# POWER.net
KiCad netlist of a schematic drawn in Altium Designer
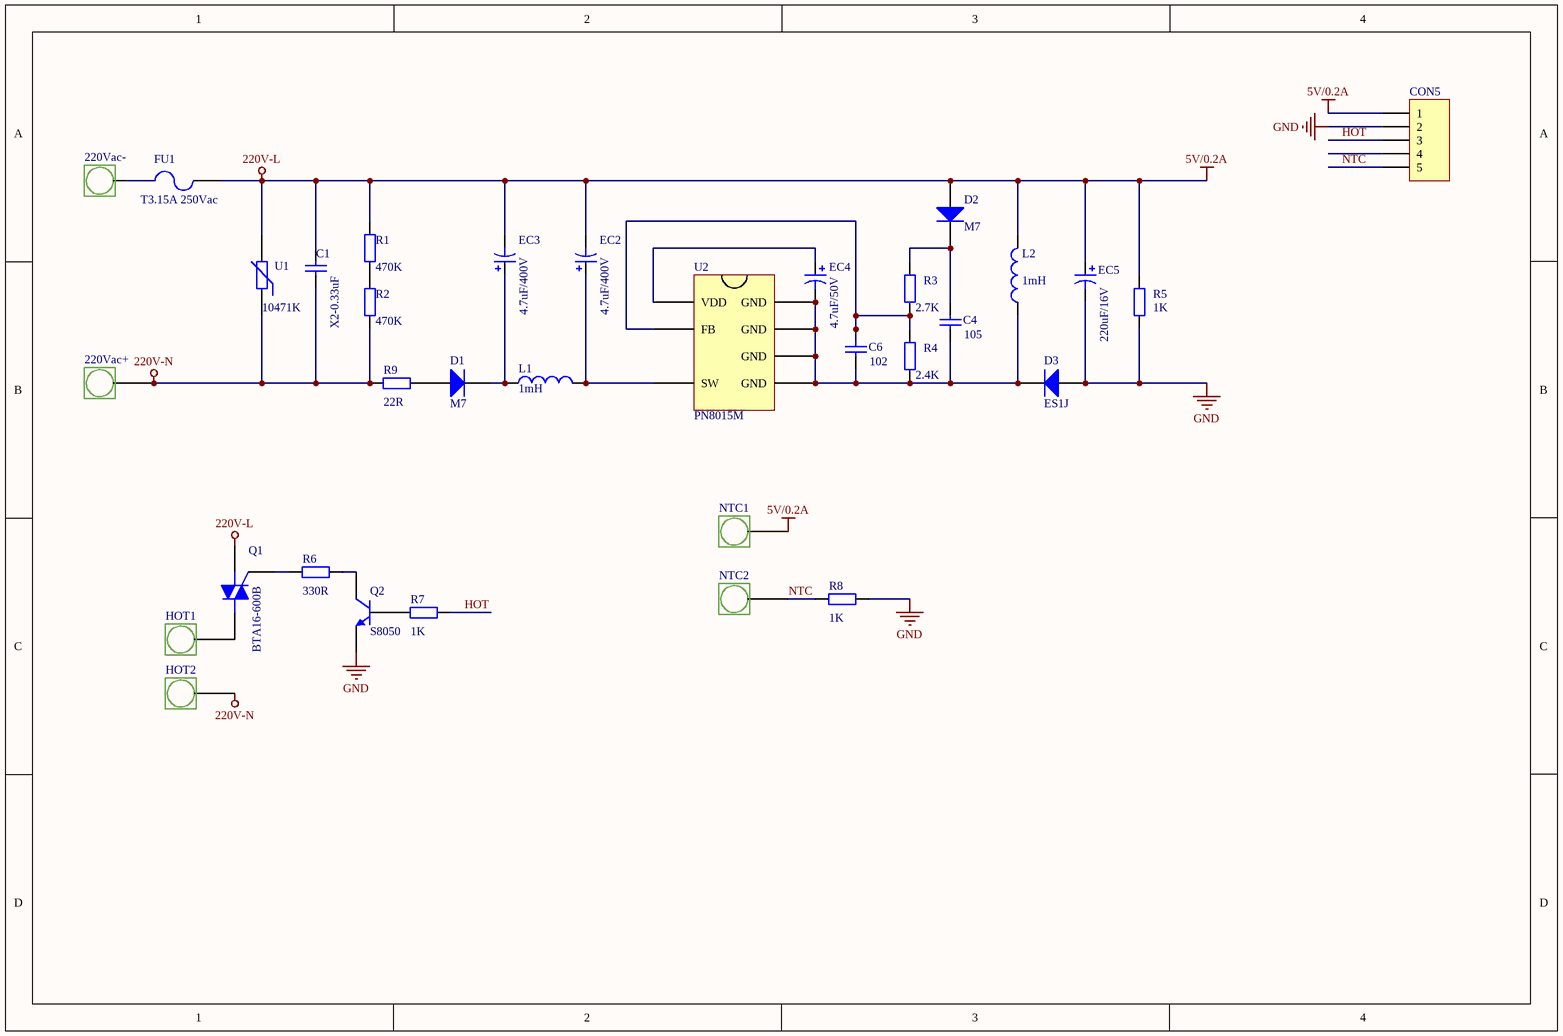
[diagram p0: POWER.SchDoc]

(export (version "E")
  (design (tool "Eeschema 10.0.6"))
  (components
    (comp (ref "220Vac+") (value "焊接点") (footprint "HanJie") (libsource (lib "HT_SHUIHU") (part "PORT")))
    (comp (ref "220Vac-") (value "焊接点") (footprint "HanJie") (libsource (lib "HT_SHUIHU") (part "PORT")))
    (comp (ref "C1")
      (value "X2-0.33uF")
      (footprint "X2-AnGuiDianRong")
      (description "Capacitor")
      (fields (field (name "PUBLISHER") "Altium Limited"))
      (libsource (lib "Miscellaneous Devices") (part "Cap"))
    )
    (comp (ref "C4")
      (value "105")
      (footprint "6-0805_N")
      (description "Capacitor")
      (fields (field (name "Comment") "电容") (field (name "PUBLISHER") "Altium Limited"))
      (libsource (lib "Miscellaneous Devices") (part "Cap"))
    )
    (comp (ref "C6")
      (value "102")
      (footprint "6-0805_N")
      (description "Capacitor")
      (fields (field (name "Comment") "电容") (field (name "PUBLISHER") "Altium Limited"))
      (libsource (lib "Miscellaneous Devices") (part "Cap"))
    )
    (comp (ref "CON5")
      (value "连接器")
      (footprint "HEADER_5")
      (description "Header, 5-Pin")
      (fields (field (name "PUBLISHER") "Altium Limited"))
      (libsource (lib "Miscellaneous Connectors") (part "Header 5"))
    )
    (comp (ref "D1")
      (value "M7")
      (footprint "ErJiGuan-M7")
      (description "1 Amp General Purpose Rectifier")
      (fields (field (name "PUBLISHER") "Altium Limited"))
      (libsource (lib "Miscellaneous Devices") (part "Diode 1N4001"))
    )
    (comp (ref "D2")
      (value "M7")
      (footprint "ErJiGuan-M7")
      (description "1 Amp General Purpose Rectifier")
      (fields (field (name "PUBLISHER") "Altium Limited"))
      (libsource (lib "Miscellaneous Devices") (part "Diode 1N4007"))
    )
    (comp (ref "D3")
      (value "ES1J")
      (footprint "ErJiGuan-M7")
      (description "Default Diode")
      (fields (field (name "PUBLISHER") "Altium Limited"))
      (libsource (lib "Miscellaneous Devices") (part "Diode"))
    )
    (comp (ref "EC2")
      (value "4.7uF/400V")
      (footprint "DianRong-3.5mm")
      (description "Polarized Capacitor (Radial)")
      (fields (field (name "Comment") "电容") (field (name "PUBLISHER") "Altium Limited"))
      (libsource (lib "Miscellaneous Devices") (part "Cap Pol1"))
    )
    (comp (ref "EC3")
      (value "4.7uF/400V")
      (footprint "DianRong-3.5mm")
      (description "Polarized Capacitor (Radial)")
      (fields (field (name "Comment") "电容") (field (name "PUBLISHER") "Altium Limited"))
      (libsource (lib "Miscellaneous Devices") (part "Cap Pol1"))
    )
    (comp (ref "EC4")
      (value "4.7uF/50V")
      (footprint "DianRong-3.3mm")
      (description "Polarized Capacitor (Radial)")
      (fields (field (name "Comment") "电容") (field (name "PUBLISHER") "Altium Limited"))
      (libsource (lib "Miscellaneous Devices") (part "Cap Pol1"))
    )
    (comp (ref "EC5")
      (value "220uF/16V")
      (footprint "DianRong-3.2mm")
      (description "Polarized Capacitor (Radial)")
      (fields (field (name "Comment") "电容") (field (name "PUBLISHER") "Altium Limited"))
      (libsource (lib "Miscellaneous Devices") (part "Cap Pol1"))
    )
    (comp (ref "FU1")
      (value "T3.15A 250Vac")
      (footprint "BaoXianSi")
      (description "Fuse")
      (fields (field (name "PUBLISHER") "Altium Limited"))
      (libsource (lib "Miscellaneous Devices") (part "Fuse 2"))
    )
    (comp (ref "HOT1") (value "焊接点") (footprint "HanJie") (libsource (lib "HT_SHUIHU") (part "PORT")))
    (comp (ref "HOT2") (value "焊接点") (footprint "HanJie") (libsource (lib "HT_SHUIHU") (part "PORT")))
    (comp (ref "L1")
      (value "1mH")
      (footprint "DianGan-12.5mm")
      (description "Inductor")
      (fields (field (name "Comment") "电感") (field (name "PUBLISHER") "Altium Limited"))
      (libsource (lib "Miscellaneous Devices") (part "Inductor"))
    )
    (comp (ref "L2")
      (value "1mH")
      (footprint "DianGan")
      (description "Inductor")
      (fields (field (name "Comment") "电感") (field (name "PUBLISHER") "Altium Limited"))
      (libsource (lib "Miscellaneous Devices") (part "Inductor"))
    )
    (comp (ref "NTC1") (value "焊接点") (footprint "HanJie") (libsource (lib "HT_SHUIHU") (part "PORT")))
    (comp (ref "NTC2") (value "焊接点") (footprint "HanJie") (libsource (lib "HT_SHUIHU") (part "PORT")))
    (comp (ref "Q1")
      (value "BTA16-600B")
      (footprint "BTA16-600B")
      (description "Silicon Bidirectional Triode Thyristor")
      (fields (field (name "PUBLISHER") "Altium Limited"))
      (libsource (lib "Miscellaneous Devices") (part "Triac"))
    )
    (comp (ref "Q2")
      (value "S8050")
      (footprint "SOT-23_L")
      (description "NPN Bipolar Transistor")
      (fields (field (name "PUBLISHER") "Altium Limited"))
      (libsource (lib "Miscellaneous Devices") (part "QNPN"))
    )
    (comp (ref "R1")
      (value "470K")
      (footprint "6-0805_N")
      (description "Resistor")
      (fields (field (name "Comment") "电阻") (field (name "PUBLISHER") "Altium Limited"))
      (libsource (lib "") (part "Res2_1"))
    )
    (comp (ref "R2")
      (value "470K")
      (footprint "6-0805_N")
      (description "Resistor")
      (fields (field (name "Comment") "电阻") (field (name "PUBLISHER") "Altium Limited"))
      (libsource (lib "") (part "Res2_1"))
    )
    (comp (ref "R3")
      (value "2.7K")
      (footprint "6-0805_N")
      (description "Resistor")
      (fields (field (name "Comment") "电阻") (field (name "PUBLISHER") "Altium Limited"))
      (libsource (lib "") (part "Res2_1"))
    )
    (comp (ref "R4")
      (value "2.4K")
      (footprint "6-0805_N")
      (description "Resistor")
      (fields (field (name "Comment") "电阻") (field (name "PUBLISHER") "Altium Limited"))
      (libsource (lib "") (part "Res2_1"))
    )
    (comp (ref "R5")
      (value "1K")
      (footprint "6-0805_N")
      (description "Resistor")
      (fields (field (name "Comment") "电阻") (field (name "PUBLISHER") "Altium Limited"))
      (libsource (lib "") (part "Res2_1"))
    )
    (comp (ref "R6")
      (value "330R")
      (footprint "6-0805_N")
      (description "Resistor")
      (fields (field (name "Comment") "电阻") (field (name "PUBLISHER") "Altium Limited"))
      (libsource (lib "Miscellaneous Devices") (part "Res2"))
    )
    (comp (ref "R7")
      (value "1K")
      (footprint "6-0805_N")
      (description "Resistor")
      (fields (field (name "Comment") "电阻") (field (name "PUBLISHER") "Altium Limited"))
      (libsource (lib "Miscellaneous Devices") (part "Res2"))
    )
    (comp (ref "R8")
      (value "1K")
      (footprint "6-0805_N")
      (description "Resistor")
      (fields (field (name "Comment") "电阻") (field (name "PUBLISHER") "Altium Limited"))
      (libsource (lib "Miscellaneous Devices") (part "Res2"))
    )
    (comp (ref "R9")
      (value "22R")
      (footprint "DianZhu-20mm")
      (description "Resistor")
      (fields (field (name "Comment") "电阻") (field (name "PUBLISHER") "Altium Limited"))
      (libsource (lib "Miscellaneous Devices") (part "Res2"))
    )
    (comp (ref "U1")
      (value "10471K")
      (footprint "YaMinDianZhu")
      (description "Varistor (Voltage-Sensitive Resistor)")
      (fields (field (name "PUBLISHER") "Altium Limited"))
      (libsource (lib "Miscellaneous Devices") (part "Res Varistor"))
    )
    (comp (ref "U2")
      (value "PN8015M")
      (footprint "SOP7-PN8015M")
      (libsource (lib "HT_SHUIHU") (part "PN8015"))
    )
  )
  (nets
    (net (code "1") (name "/HOT") (class "Default")
      (node (ref "CON5") (pin "3") (pinfunction "3_3") (pintype "passive"))
      (node (ref "R7") (pin "2") (pinfunction "2_2") (pintype "passive"))
    )
    (net (code "2") (name "/NTC") (class "Default")
      (node (ref "CON5") (pin "5") (pinfunction "5_5") (pintype "passive"))
      (node (ref "NTC2") (pin "1") (pinfunction "P_1") (pintype "passive"))
      (node (ref "R8") (pin "1") (pinfunction "1_1") (pintype "passive"))
    )
    (net (code "3") (name "220V-L") (class "Default")
      (node (ref "C1") (pin "2") (pinfunction "2_2") (pintype "passive"))
      (node (ref "CON5") (pin "1") (pinfunction "1_1") (pintype "passive"))
      (node (ref "D2") (pin "1") (pinfunction "A_1") (pintype "passive"))
      (node (ref "EC2") (pin "2") (pinfunction "2_2") (pintype "passive"))
      (node (ref "EC3") (pin "2") (pinfunction "2_2") (pintype "passive"))
      (node (ref "EC5") (pin "1") (pinfunction "1_1") (pintype "passive"))
      (node (ref "FU1") (pin "2") (pinfunction "2_2") (pintype "passive"))
      (node (ref "L2") (pin "2") (pinfunction "2_2") (pintype "passive"))
      (node (ref "NTC1") (pin "1") (pinfunction "P_1") (pintype "passive"))
      (node (ref "Q1") (pin "1") (pinfunction "M1_1") (pintype "passive"))
      (node (ref "R1") (pin "2") (pinfunction "2_2") (pintype "passive"))
      (node (ref "R5") (pin "2") (pinfunction "2_2") (pintype "passive"))
      (node (ref "U1") (pin "2") (pinfunction "2_2") (pintype "passive"))
    )
    (net (code "4") (name "220V-N") (class "Default")
      (node (ref "220Vac+") (pin "1") (pinfunction "P_1") (pintype "passive"))
      (node (ref "C1") (pin "1") (pinfunction "1_1") (pintype "passive"))
      (node (ref "HOT2") (pin "1") (pinfunction "P_1") (pintype "passive"))
      (node (ref "R2") (pin "1") (pinfunction "1_1") (pintype "passive"))
      (node (ref "R9") (pin "1") (pinfunction "1_1") (pintype "passive"))
      (node (ref "U1") (pin "1") (pinfunction "1_1") (pintype "passive"))
    )
    (net (code "5") (name "GND") (class "Default")
      (node (ref "CON5") (pin "2") (pinfunction "2_2") (pintype "passive"))
      (node (ref "D3") (pin "1") (pinfunction "A_1") (pintype "passive"))
      (node (ref "EC5") (pin "2") (pinfunction "2_2") (pintype "passive"))
      (node (ref "Q2") (pin "2") (pinfunction "E_2") (pintype "passive"))
      (node (ref "R5") (pin "1") (pinfunction "1_1") (pintype "passive"))
      (node (ref "R8") (pin "2") (pinfunction "2_2") (pintype "passive"))
    )
    (net (code "6") (name "Net-(220Vac--P)") (class "Default")
      (node (ref "220Vac-") (pin "1") (pinfunction "P_1") (pintype "passive"))
      (node (ref "FU1") (pin "1") (pinfunction "1_1") (pintype "passive"))
    )
    (net (code "7") (name "Net-(D1-A)") (class "Default")
      (node (ref "D1") (pin "1") (pinfunction "A_1") (pintype "passive"))
      (node (ref "R9") (pin "2") (pinfunction "2_2") (pintype "passive"))
    )
    (net (code "8") (name "Net-(D1-K)") (class "Default")
      (node (ref "D1") (pin "2") (pinfunction "K_2") (pintype "passive"))
      (node (ref "EC3") (pin "1") (pinfunction "1_1") (pintype "passive"))
      (node (ref "L1") (pin "1") (pinfunction "1_1") (pintype "passive"))
    )
    (net (code "9") (name "Net-(D2-K)") (class "Default")
      (node (ref "C4") (pin "2") (pinfunction "2_2") (pintype "passive"))
      (node (ref "D2") (pin "2") (pinfunction "K_2") (pintype "passive"))
      (node (ref "R3") (pin "2") (pinfunction "2_2") (pintype "passive"))
    )
    (net (code "10") (name "Net-(D3-K)") (class "Default")
      (node (ref "C4") (pin "1") (pinfunction "1_1") (pintype "passive"))
      (node (ref "C6") (pin "1") (pinfunction "1_1") (pintype "passive"))
      (node (ref "D3") (pin "2") (pinfunction "K_2") (pintype "passive"))
      (node (ref "EC4") (pin "2") (pinfunction "2_2") (pintype "passive"))
      (node (ref "L2") (pin "1") (pinfunction "1_1") (pintype "passive"))
      (node (ref "R4") (pin "1") (pinfunction "1_1") (pintype "passive"))
      (node (ref "U2") (pin "4") (pinfunction "GND_4") (pintype "passive"))
      (node (ref "U2") (pin "5") (pinfunction "GND_5") (pintype "passive"))
      (node (ref "U2") (pin "6") (pinfunction "GND_6") (pintype "passive"))
      (node (ref "U2") (pin "7") (pinfunction "GND_7") (pintype "passive"))
    )
    (net (code "11") (name "Net-(HOT1-P)") (class "Default")
      (node (ref "HOT1") (pin "1") (pinfunction "P_1") (pintype "passive"))
      (node (ref "Q1") (pin "2") (pinfunction "M2_2") (pintype "passive"))
    )
    (net (code "12") (name "Net-(Q1-G)") (class "Default")
      (node (ref "Q1") (pin "3") (pinfunction "G_3") (pintype "passive"))
      (node (ref "R6") (pin "1") (pinfunction "1_1") (pintype "passive"))
    )
    (net (code "13") (name "Net-(Q2-B)") (class "Default")
      (node (ref "Q2") (pin "1") (pinfunction "B_1") (pintype "passive"))
      (node (ref "R7") (pin "1") (pinfunction "1_1") (pintype "passive"))
    )
    (net (code "14") (name "Net-(Q2-C)") (class "Default")
      (node (ref "Q2") (pin "3") (pinfunction "C_3") (pintype "passive"))
      (node (ref "R6") (pin "2") (pinfunction "2_2") (pintype "passive"))
    )
    (net (code "15") (name "Net-(R1-Pad1)") (class "Default")
      (node (ref "R1") (pin "1") (pinfunction "1_1") (pintype "passive"))
      (node (ref "R2") (pin "2") (pinfunction "2_2") (pintype "passive"))
    )
    (net (code "16") (name "Net-(U2-FB)") (class "Default")
      (node (ref "C6") (pin "2") (pinfunction "2_2") (pintype "passive"))
      (node (ref "R3") (pin "1") (pinfunction "1_1") (pintype "passive"))
      (node (ref "R4") (pin "2") (pinfunction "2_2") (pintype "passive"))
      (node (ref "U2") (pin "2") (pinfunction "FB_2") (pintype "passive"))
    )
    (net (code "17") (name "Net-(U2-SW)") (class "Default")
      (node (ref "EC2") (pin "1") (pinfunction "1_1") (pintype "passive"))
      (node (ref "L1") (pin "2") (pinfunction "2_2") (pintype "passive"))
      (node (ref "U2") (pin "3") (pinfunction "SW_3") (pintype "passive"))
    )
    (net (code "18") (name "Net-(U2-VDD)") (class "Default")
      (node (ref "EC4") (pin "1") (pinfunction "1_1") (pintype "passive"))
      (node (ref "U2") (pin "1") (pinfunction "VDD_1") (pintype "passive"))
    )
    (net (code "19") (name "unconnected-(CON5-Pad4)") (class "Default")
      (node (ref "CON5") (pin "4") (pinfunction "4_4") (pintype "passive"))
    )
  )
)
